# VelostatTest.net
KiCad netlist of a schematic drawn in Altium Designer
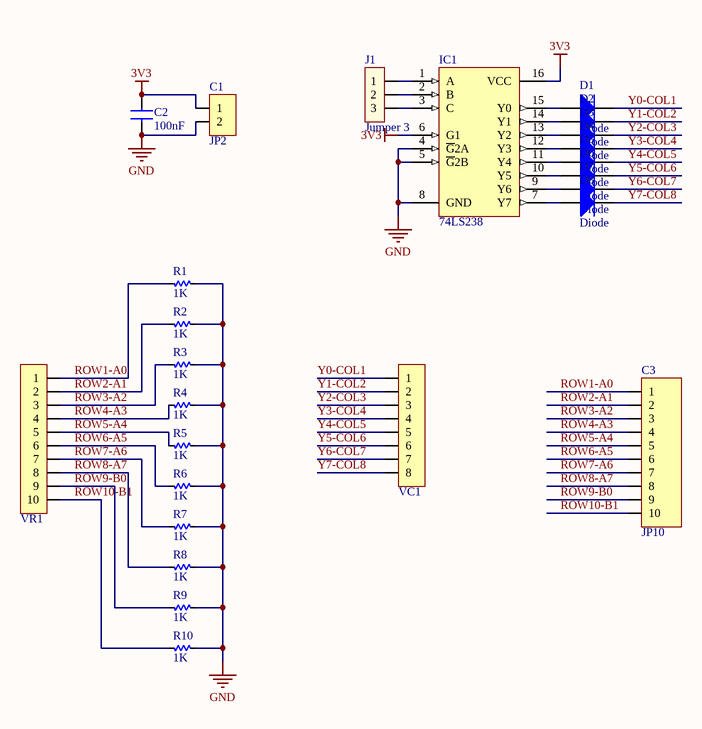
[diagram p0: VelostatTest.SchDoc]

(export (version "E")
  (design (tool "Eeschema 10.0.6"))
  (components
    (comp (ref "C1")
      (value "JP2")
      (footprint "JP2-D1T")
      (description "WR-PHD 2.54 mm Angled Socket Header")
      (fields
        (field (name "MANUFACTURER") "Würth Elektronik eiSos GmbH")
        (field (name "PARTNO") "613002143121")
        (field (name "CREATED BY") "Karrer Zheng")
      )
      (libsource (lib "My Library") (part "JP2"))
    )
    (comp (ref "C2")
      (value "Capacitor 0805")
      (footprint "vanthinh:C0805-2.01-1.25-0.94")
      (description "CAP CER 50V 0805")
      (fields
        (field (name "MANUFACTURER") "Panasonic")
        (field (name "MANUFACTURER PART NUMBER") "ECJ-2FB1H104K")
        (field (name "CAPACITANCE") "100nF")
      )
      (libsource (lib "vanthinh") (part "CAP 0805"))
    )
    (comp (ref "C3")
      (value "JP10")
      (footprint "JP10-D1T")
      (description "WR-PHD 2.54 mm Angled Socket Header")
      (fields
        (field (name "MANUFACTURER") "Würth Elektronik eiSos GmbH")
        (field (name "PARTNO") "613010143121")
        (field (name "CREATED BY") "Karrer Zheng")
      )
      (libsource (lib "Phương Trang") (part "JP10"))
    )
    (comp (ref "D1")
      (value "Diode")
      (footprint "vanthinh:SOD-123F")
      (description "Default Diode")
      (fields (field (name "PUBLISHER") "Altium Limited"))
      (libsource (lib "vanthinh") (part "DIODE"))
    )
    (comp (ref "D2")
      (value "Diode")
      (footprint "vanthinh:SOD-123F")
      (description "Default Diode")
      (fields (field (name "PUBLISHER") "Altium Limited"))
      (libsource (lib "vanthinh") (part "DIODE"))
    )
    (comp (ref "D3")
      (value "Diode")
      (footprint "vanthinh:SOD-123F")
      (description "Default Diode")
      (fields (field (name "PUBLISHER") "Altium Limited"))
      (libsource (lib "vanthinh") (part "DIODE"))
    )
    (comp (ref "D4")
      (value "Diode")
      (footprint "vanthinh:SOD-123F")
      (description "Default Diode")
      (fields (field (name "PUBLISHER") "Altium Limited"))
      (libsource (lib "vanthinh") (part "DIODE"))
    )
    (comp (ref "D5")
      (value "Diode")
      (footprint "vanthinh:SOD-123F")
      (description "Default Diode")
      (fields (field (name "PUBLISHER") "Altium Limited"))
      (libsource (lib "vanthinh") (part "DIODE"))
    )
    (comp (ref "D6")
      (value "Diode")
      (footprint "vanthinh:SOD-123F")
      (description "Default Diode")
      (fields (field (name "PUBLISHER") "Altium Limited"))
      (libsource (lib "vanthinh") (part "DIODE"))
    )
    (comp (ref "D7")
      (value "Diode")
      (footprint "vanthinh:SOD-123F")
      (description "Default Diode")
      (fields (field (name "PUBLISHER") "Altium Limited"))
      (libsource (lib "vanthinh") (part "DIODE"))
    )
    (comp (ref "D8")
      (value "Diode")
      (footprint "vanthinh:SOD-123F")
      (description "Default Diode")
      (fields (field (name "PUBLISHER") "Altium Limited"))
      (libsource (lib "vanthinh") (part "DIODE"))
    )
    (comp (ref "IC1")
      (value "74LS238")
      (footprint "SO16")
      (description "3 -to- 8 Decoder - Out High")
      (fields (field (name "COPYRIGHT BY") "VanDungEvn@Gmail.com"))
      (libsource (lib "LIBRARY") (part "74238"))
    )
    (comp (ref "J1") (value "Jumper 3") (footprint "JP3") (libsource (lib "Cty1") (part "JP3")))
    (comp (ref "R1")
      (value "Resistor 0805")
      (footprint "vanthinh:R0805")
      (description "TE CONNECTIVITY / CGS - RH73H2A100MKTN - RES, THICK FILM, 100M, 10%, 0.125W, 0805")
      (fields
        (field (name "MANUFACTURER") "TE Connectivity")
        (field (name "MANUFACTURER PART NUMBER") "RH73H2A100MKTN")
        (field (name "RESISTANCE") "1K")
      )
      (libsource (lib "vanthinh") (part "RES 0805"))
    )
    (comp (ref "R2")
      (value "Resistor 0805")
      (footprint "vanthinh:R0805")
      (description "TE CONNECTIVITY / CGS - RH73H2A100MKTN - RES, THICK FILM, 100M, 10%, 0.125W, 0805")
      (fields
        (field (name "MANUFACTURER") "TE Connectivity")
        (field (name "MANUFACTURER PART NUMBER") "RH73H2A100MKTN")
        (field (name "RESISTANCE") "1K")
      )
      (libsource (lib "vanthinh") (part "RES 0805"))
    )
    (comp (ref "R3")
      (value "Resistor 0805")
      (footprint "vanthinh:R0805")
      (description "TE CONNECTIVITY / CGS - RH73H2A100MKTN - RES, THICK FILM, 100M, 10%, 0.125W, 0805")
      (fields
        (field (name "MANUFACTURER") "TE Connectivity")
        (field (name "MANUFACTURER PART NUMBER") "RH73H2A100MKTN")
        (field (name "RESISTANCE") "1K")
      )
      (libsource (lib "vanthinh") (part "RES 0805"))
    )
    (comp (ref "R4")
      (value "Resistor 0805")
      (footprint "vanthinh:R0805")
      (description "TE CONNECTIVITY / CGS - RH73H2A100MKTN - RES, THICK FILM, 100M, 10%, 0.125W, 0805")
      (fields
        (field (name "MANUFACTURER") "TE Connectivity")
        (field (name "MANUFACTURER PART NUMBER") "RH73H2A100MKTN")
        (field (name "RESISTANCE") "1K")
      )
      (libsource (lib "vanthinh") (part "RES 0805"))
    )
    (comp (ref "R5")
      (value "Resistor 0805")
      (footprint "vanthinh:R0805")
      (description "TE CONNECTIVITY / CGS - RH73H2A100MKTN - RES, THICK FILM, 100M, 10%, 0.125W, 0805")
      (fields
        (field (name "MANUFACTURER") "TE Connectivity")
        (field (name "MANUFACTURER PART NUMBER") "RH73H2A100MKTN")
        (field (name "RESISTANCE") "1K")
      )
      (libsource (lib "vanthinh") (part "RES 0805"))
    )
    (comp (ref "R6")
      (value "Resistor 0805")
      (footprint "vanthinh:R0805")
      (description "TE CONNECTIVITY / CGS - RH73H2A100MKTN - RES, THICK FILM, 100M, 10%, 0.125W, 0805")
      (fields
        (field (name "MANUFACTURER") "TE Connectivity")
        (field (name "MANUFACTURER PART NUMBER") "RH73H2A100MKTN")
        (field (name "RESISTANCE") "1K")
      )
      (libsource (lib "vanthinh") (part "RES 0805"))
    )
    (comp (ref "R7")
      (value "Resistor 0805")
      (footprint "vanthinh:R0805")
      (description "TE CONNECTIVITY / CGS - RH73H2A100MKTN - RES, THICK FILM, 100M, 10%, 0.125W, 0805")
      (fields
        (field (name "MANUFACTURER") "TE Connectivity")
        (field (name "MANUFACTURER PART NUMBER") "RH73H2A100MKTN")
        (field (name "RESISTANCE") "1K")
      )
      (libsource (lib "vanthinh") (part "RES 0805"))
    )
    (comp (ref "R8")
      (value "Resistor 0805")
      (footprint "vanthinh:R0805")
      (description "TE CONNECTIVITY / CGS - RH73H2A100MKTN - RES, THICK FILM, 100M, 10%, 0.125W, 0805")
      (fields
        (field (name "MANUFACTURER") "TE Connectivity")
        (field (name "MANUFACTURER PART NUMBER") "RH73H2A100MKTN")
        (field (name "RESISTANCE") "1K")
      )
      (libsource (lib "vanthinh") (part "RES 0805"))
    )
    (comp (ref "R9")
      (value "Resistor 0805")
      (footprint "vanthinh:R0805")
      (description "TE CONNECTIVITY / CGS - RH73H2A100MKTN - RES, THICK FILM, 100M, 10%, 0.125W, 0805")
      (fields
        (field (name "MANUFACTURER") "TE Connectivity")
        (field (name "MANUFACTURER PART NUMBER") "RH73H2A100MKTN")
        (field (name "RESISTANCE") "1K")
      )
      (libsource (lib "vanthinh") (part "RES 0805"))
    )
    (comp (ref "R10")
      (value "Resistor 0805")
      (footprint "vanthinh:R0805")
      (description "TE CONNECTIVITY / CGS - RH73H2A100MKTN - RES, THICK FILM, 100M, 10%, 0.125W, 0805")
      (fields
        (field (name "MANUFACTURER") "TE Connectivity")
        (field (name "MANUFACTURER PART NUMBER") "RH73H2A100MKTN")
        (field (name "RESISTANCE") "1K")
      )
      (libsource (lib "vanthinh") (part "RES 0805"))
    )
    (comp (ref "VC1")
      (value "VELOSTAT COL")
      (footprint "VELOSTAT COL")
      (description "8 columns to test a sensor with 8x8 dot matrix")
      (libsource (lib "VelostatTest") (part "VELOSTAT COL"))
    )
    (comp (ref "VR1")
      (value "VELOSTAT ROW")
      (footprint "VELOSTAT ROW")
      (description "10 rows to test a sensor with 8x8 dot matrix")
      (libsource (lib "VelostatTest") (part "VELOSTAT ROW"))
    )
  )
  (nets
    (net (code "1") (name "/ROW1-A0") (class "Default")
      (node (ref "C3") (pin "1") (pinfunction "1_1") (pintype "passive"))
      (node (ref "R1") (pin "1") (pinfunction "1_1") (pintype "passive"))
      (node (ref "VR1") (pin "1") (pinfunction "1_1") (pintype "passive"))
    )
    (net (code "2") (name "/ROW2-A1") (class "Default")
      (node (ref "C3") (pin "2") (pinfunction "2_2") (pintype "passive"))
      (node (ref "R2") (pin "1") (pinfunction "1_1") (pintype "passive"))
      (node (ref "VR1") (pin "2") (pinfunction "2_2") (pintype "passive"))
    )
    (net (code "3") (name "/ROW3-A2") (class "Default")
      (node (ref "C3") (pin "3") (pinfunction "3_3") (pintype "passive"))
      (node (ref "R3") (pin "1") (pinfunction "1_1") (pintype "passive"))
      (node (ref "VR1") (pin "3") (pinfunction "3_3") (pintype "passive"))
    )
    (net (code "4") (name "/ROW4-A3") (class "Default")
      (node (ref "C3") (pin "4") (pinfunction "4_4") (pintype "passive"))
      (node (ref "R4") (pin "1") (pinfunction "1_1") (pintype "passive"))
      (node (ref "VR1") (pin "4") (pinfunction "4_4") (pintype "passive"))
    )
    (net (code "5") (name "/ROW5-A4") (class "Default")
      (node (ref "C3") (pin "5") (pinfunction "5_5") (pintype "passive"))
      (node (ref "R5") (pin "1") (pinfunction "1_1") (pintype "passive"))
      (node (ref "VR1") (pin "5") (pinfunction "5_5") (pintype "passive"))
    )
    (net (code "6") (name "/ROW6-A5") (class "Default")
      (node (ref "C3") (pin "6") (pinfunction "6_6") (pintype "passive"))
      (node (ref "R6") (pin "1") (pinfunction "1_1") (pintype "passive"))
      (node (ref "VR1") (pin "6") (pinfunction "6_6") (pintype "passive"))
    )
    (net (code "7") (name "/ROW7-A6") (class "Default")
      (node (ref "C3") (pin "7") (pinfunction "7_7") (pintype "passive"))
      (node (ref "R7") (pin "1") (pinfunction "1_1") (pintype "passive"))
      (node (ref "VR1") (pin "7") (pinfunction "7_7") (pintype "passive"))
    )
    (net (code "8") (name "/ROW8-A7") (class "Default")
      (node (ref "C3") (pin "8") (pinfunction "8_8") (pintype "passive"))
      (node (ref "R8") (pin "1") (pinfunction "1_1") (pintype "passive"))
      (node (ref "VR1") (pin "8") (pinfunction "8_8") (pintype "passive"))
    )
    (net (code "9") (name "/ROW9-B0") (class "Default")
      (node (ref "C3") (pin "9") (pinfunction "9_9") (pintype "passive"))
      (node (ref "R9") (pin "1") (pinfunction "1_1") (pintype "passive"))
      (node (ref "VR1") (pin "9") (pinfunction "9_9") (pintype "passive"))
    )
    (net (code "10") (name "/ROW10-B1") (class "Default")
      (node (ref "C3") (pin "10") (pinfunction "10_10") (pintype "passive"))
      (node (ref "R10") (pin "1") (pinfunction "1_1") (pintype "passive"))
      (node (ref "VR1") (pin "10") (pinfunction "10_10") (pintype "passive"))
    )
    (net (code "11") (name "/Y0-COL1") (class "Default")
      (node (ref "D1") (pin "2") (pinfunction "K_2") (pintype "passive"))
      (node (ref "VC1") (pin "1") (pinfunction "1_1") (pintype "passive"))
    )
    (net (code "12") (name "/Y1-COL2") (class "Default")
      (node (ref "D2") (pin "2") (pinfunction "K_2") (pintype "passive"))
      (node (ref "VC1") (pin "2") (pinfunction "2_2") (pintype "passive"))
    )
    (net (code "13") (name "/Y3-COL4") (class "Default")
      (node (ref "D4") (pin "2") (pinfunction "K_2") (pintype "passive"))
      (node (ref "VC1") (pin "4") (pinfunction "4_4") (pintype "passive"))
    )
    (net (code "14") (name "/Y4-COL5") (class "Default")
      (node (ref "D5") (pin "2") (pinfunction "K_2") (pintype "passive"))
      (node (ref "VC1") (pin "5") (pinfunction "5_5") (pintype "passive"))
    )
    (net (code "15") (name "/Y5-COL6") (class "Default")
      (node (ref "D6") (pin "2") (pinfunction "K_2") (pintype "passive"))
      (node (ref "VC1") (pin "6") (pinfunction "6_6") (pintype "passive"))
    )
    (net (code "16") (name "/Y6-COL7") (class "Default")
      (node (ref "D7") (pin "2") (pinfunction "K_2") (pintype "passive"))
      (node (ref "VC1") (pin "7") (pinfunction "7_7") (pintype "passive"))
    )
    (net (code "17") (name "/Y7-COL8") (class "Default")
      (node (ref "D8") (pin "2") (pinfunction "K_2") (pintype "passive"))
      (node (ref "VC1") (pin "8") (pinfunction "8_8") (pintype "passive"))
    )
    (net (code "18") (name "/Y~{2}-COL3") (class "Default")
      (node (ref "D3") (pin "2") (pinfunction "K_2") (pintype "passive"))
      (node (ref "VC1") (pin "3") (pinfunction "3_3") (pintype "passive"))
    )
    (net (code "19") (name "3V3") (class "Default")
      (node (ref "C1") (pin "1") (pinfunction "1_1") (pintype "passive"))
      (node (ref "C2") (pin "2") (pinfunction "2_2") (pintype "passive"))
      (node (ref "IC1") (pin "16") (pinfunction "VCC_16") (pintype "power_in"))
      (node (ref "IC1") (pin "6") (pinfunction "G1_6") (pintype "input"))
    )
    (net (code "20") (name "GND") (class "Default")
      (node (ref "C1") (pin "2") (pinfunction "2_2") (pintype "passive"))
      (node (ref "C2") (pin "1") (pinfunction "1_1") (pintype "passive"))
      (node (ref "IC1") (pin "4") (pinfunction "~{G}2A_4") (pintype "input"))
      (node (ref "IC1") (pin "5") (pinfunction "~{G}2B_5") (pintype "input"))
      (node (ref "IC1") (pin "8") (pinfunction "GND_8") (pintype "power_in"))
      (node (ref "R1") (pin "2") (pinfunction "2_2") (pintype "passive"))
      (node (ref "R10") (pin "2") (pinfunction "2_2") (pintype "passive"))
      (node (ref "R2") (pin "2") (pinfunction "2_2") (pintype "passive"))
      (node (ref "R3") (pin "2") (pinfunction "2_2") (pintype "passive"))
      (node (ref "R4") (pin "2") (pinfunction "2_2") (pintype "passive"))
      (node (ref "R5") (pin "2") (pinfunction "2_2") (pintype "passive"))
      (node (ref "R6") (pin "2") (pinfunction "2_2") (pintype "passive"))
      (node (ref "R7") (pin "2") (pinfunction "2_2") (pintype "passive"))
      (node (ref "R8") (pin "2") (pinfunction "2_2") (pintype "passive"))
      (node (ref "R9") (pin "2") (pinfunction "2_2") (pintype "passive"))
    )
    (net (code "21") (name "Net-(D1-A)") (class "Default")
      (node (ref "D1") (pin "1") (pinfunction "A_1") (pintype "passive"))
      (node (ref "IC1") (pin "15") (pinfunction "Y0_15") (pintype "output"))
    )
    (net (code "22") (name "Net-(D2-A)") (class "Default")
      (node (ref "D2") (pin "1") (pinfunction "A_1") (pintype "passive"))
      (node (ref "IC1") (pin "14") (pinfunction "Y1_14") (pintype "output"))
    )
    (net (code "23") (name "Net-(D3-A)") (class "Default")
      (node (ref "D3") (pin "1") (pinfunction "A_1") (pintype "passive"))
      (node (ref "IC1") (pin "13") (pinfunction "Y2_13") (pintype "output"))
    )
    (net (code "24") (name "Net-(D4-A)") (class "Default")
      (node (ref "D4") (pin "1") (pinfunction "A_1") (pintype "passive"))
      (node (ref "IC1") (pin "12") (pinfunction "Y3_12") (pintype "output"))
    )
    (net (code "25") (name "Net-(D5-A)") (class "Default")
      (node (ref "D5") (pin "1") (pinfunction "A_1") (pintype "passive"))
      (node (ref "IC1") (pin "11") (pinfunction "Y4_11") (pintype "output"))
    )
    (net (code "26") (name "Net-(D6-A)") (class "Default")
      (node (ref "D6") (pin "1") (pinfunction "A_1") (pintype "passive"))
      (node (ref "IC1") (pin "10") (pinfunction "Y5_10") (pintype "output"))
    )
    (net (code "27") (name "Net-(D7-A)") (class "Default")
      (node (ref "D7") (pin "1") (pinfunction "A_1") (pintype "passive"))
      (node (ref "IC1") (pin "9") (pinfunction "Y6_9") (pintype "output"))
    )
    (net (code "28") (name "Net-(D8-A)") (class "Default")
      (node (ref "D8") (pin "1") (pinfunction "A_1") (pintype "passive"))
      (node (ref "IC1") (pin "7") (pinfunction "Y7_7") (pintype "output"))
    )
    (net (code "29") (name "Net-(IC1-A)") (class "Default")
      (node (ref "IC1") (pin "1") (pinfunction "A_1") (pintype "input"))
      (node (ref "J1") (pin "1") (pinfunction "1_1") (pintype "passive"))
    )
    (net (code "30") (name "Net-(IC1-B)") (class "Default")
      (node (ref "IC1") (pin "2") (pinfunction "B_2") (pintype "input"))
      (node (ref "J1") (pin "2") (pinfunction "2_2") (pintype "passive"))
    )
    (net (code "31") (name "Net-(IC1-C)") (class "Default")
      (node (ref "IC1") (pin "3") (pinfunction "C_3") (pintype "input"))
      (node (ref "J1") (pin "3") (pinfunction "3_3") (pintype "passive"))
    )
  )
)
